# motor_drivers.net
KiCad netlist of a schematic drawn in Altium Designer
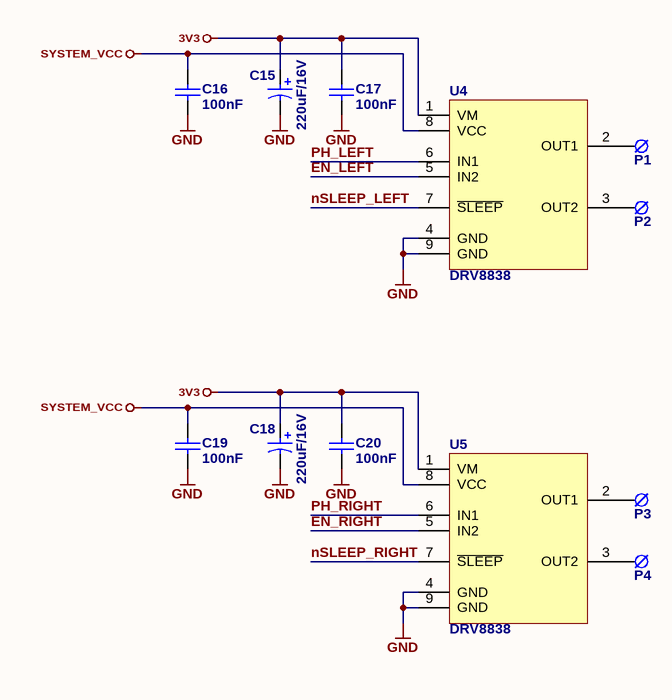
[diagram p0: motor_drivers.SchDoc]

(export (version "E")
  (design (tool "Eeschema 10.0.6"))
  (components
    (comp (ref "C15")
      (value "220uF/16V")
      (footprint "CES_E_8.3x8.3_6.2")
      (description "Polarized Capacitor")
      (libsource (lib "capacitors") (part "Cap Pol"))
    )
    (comp (ref "C16")
      (value "100nF")
      (footprint "C0805")
      (description "Capacitor")
      (libsource (lib "capacitors") (part "Cap"))
    )
    (comp (ref "C17")
      (value "100nF")
      (footprint "C0805")
      (description "Capacitor")
      (libsource (lib "capacitors") (part "Cap"))
    )
    (comp (ref "C18")
      (value "220uF/16V")
      (footprint "CES_E_8.3x8.3_6.2")
      (description "Polarized Capacitor")
      (libsource (lib "capacitors") (part "Cap Pol"))
    )
    (comp (ref "C19")
      (value "100nF")
      (footprint "C0805")
      (description "Capacitor")
      (libsource (lib "capacitors") (part "Cap"))
    )
    (comp (ref "C20")
      (value "100nF")
      (footprint "C0805")
      (description "Capacitor")
      (libsource (lib "capacitors") (part "Cap"))
    )
    (comp (ref "P1")
      (value "CablePAD")
      (footprint "PADTHT1.5x3mm")
      (description "Cable/Wire Soldering PAD")
      (libsource (lib "wire_and_cable_pads") (part "CablePAD"))
    )
    (comp (ref "P2")
      (value "CablePAD")
      (footprint "PADTHT1.5x3mm")
      (description "Cable/Wire Soldering PAD")
      (libsource (lib "wire_and_cable_pads") (part "CablePAD"))
    )
    (comp (ref "P3")
      (value "CablePAD")
      (footprint "PADTHT1.5x3mm")
      (description "Cable/Wire Soldering PAD")
      (libsource (lib "wire_and_cable_pads") (part "CablePAD"))
    )
    (comp (ref "P4")
      (value "CablePAD")
      (footprint "PADTHT1.5x3mm")
      (description "Cable/Wire Soldering PAD")
      (libsource (lib "wire_and_cable_pads") (part "CablePAD"))
    )
    (comp (ref "U4")
      (value "DRV8838")
      (footprint "WSON8 (DSG8-1600X900TP)")
      (description "Low-Voltage H-Bridge Driver")
      (libsource (lib "motor_drivers") (part "DRV8838"))
    )
    (comp (ref "U5")
      (value "DRV8838")
      (footprint "WSON8 (DSG8-1600X900TP)")
      (description "Low-Voltage H-Bridge Driver")
      (libsource (lib "motor_drivers") (part "DRV8838"))
    )
  )
  (nets
    (net (code "1") (name "/EN_LEFT") (class "Default")
      (node (ref "U4") (pin "5") (pinfunction "IN2_5") (pintype "passive"))
    )
    (net (code "2") (name "/EN_RIGHT") (class "Default")
      (node (ref "U5") (pin "5") (pinfunction "IN2_5") (pintype "passive"))
    )
    (net (code "3") (name "/PH_LEFT") (class "Default")
      (node (ref "U4") (pin "6") (pinfunction "IN1_6") (pintype "passive"))
    )
    (net (code "4") (name "/PH_RIGHT") (class "Default")
      (node (ref "U5") (pin "6") (pinfunction "IN1_6") (pintype "passive"))
    )
    (net (code "5") (name "/nSLEEP_LEFT") (class "Default")
      (node (ref "U4") (pin "7") (pinfunction "~{SLEEP}_7") (pintype "passive"))
    )
    (net (code "6") (name "/nSLEEP_RIGHT") (class "Default")
      (node (ref "U5") (pin "7") (pinfunction "~{SLEEP}_7") (pintype "passive"))
    )
    (net (code "7") (name "3V3") (class "Default")
      (node (ref "C15") (pin "1") (pinfunction "1_1") (pintype "passive"))
      (node (ref "C17") (pin "2") (pinfunction "2_2") (pintype "passive"))
      (node (ref "C18") (pin "1") (pinfunction "1_1") (pintype "passive"))
      (node (ref "C20") (pin "2") (pinfunction "2_2") (pintype "passive"))
      (node (ref "U4") (pin "1") (pinfunction "VM_1") (pintype "passive"))
      (node (ref "U5") (pin "1") (pinfunction "VM_1") (pintype "passive"))
    )
    (net (code "8") (name "GND") (class "Default")
      (node (ref "C15") (pin "2") (pinfunction "2_2") (pintype "passive"))
      (node (ref "C16") (pin "1") (pinfunction "1_1") (pintype "passive"))
      (node (ref "C17") (pin "1") (pinfunction "1_1") (pintype "passive"))
      (node (ref "C18") (pin "2") (pinfunction "2_2") (pintype "passive"))
      (node (ref "C19") (pin "1") (pinfunction "1_1") (pintype "passive"))
      (node (ref "C20") (pin "1") (pinfunction "1_1") (pintype "passive"))
      (node (ref "U4") (pin "4") (pinfunction "GND_4") (pintype "passive"))
      (node (ref "U4") (pin "9") (pinfunction "GND_9") (pintype "passive"))
      (node (ref "U5") (pin "4") (pinfunction "GND_4") (pintype "passive"))
      (node (ref "U5") (pin "9") (pinfunction "GND_9") (pintype "passive"))
    )
    (net (code "9") (name "Net-(U4-OUT1)") (class "Default")
      (node (ref "P1") (pin "0") (pinfunction "0_0") (pintype "passive"))
      (node (ref "U4") (pin "2") (pinfunction "OUT1_2") (pintype "passive"))
    )
    (net (code "10") (name "Net-(U4-OUT2)") (class "Default")
      (node (ref "P2") (pin "0") (pinfunction "0_0") (pintype "passive"))
      (node (ref "U4") (pin "3") (pinfunction "OUT2_3") (pintype "passive"))
    )
    (net (code "11") (name "Net-(U5-OUT1)") (class "Default")
      (node (ref "P3") (pin "0") (pinfunction "0_0") (pintype "passive"))
      (node (ref "U5") (pin "2") (pinfunction "OUT1_2") (pintype "passive"))
    )
    (net (code "12") (name "Net-(U5-OUT2)") (class "Default")
      (node (ref "P4") (pin "0") (pinfunction "0_0") (pintype "passive"))
      (node (ref "U5") (pin "3") (pinfunction "OUT2_3") (pintype "passive"))
    )
    (net (code "13") (name "SYSTEM_VCC") (class "Default")
      (node (ref "C16") (pin "2") (pinfunction "2_2") (pintype "passive"))
      (node (ref "C19") (pin "2") (pinfunction "2_2") (pintype "passive"))
      (node (ref "U4") (pin "8") (pinfunction "VCC_8") (pintype "passive"))
      (node (ref "U5") (pin "8") (pinfunction "VCC_8") (pintype "passive"))
    )
  )
)
